# Battery_Charger.net
KiCad netlist of a schematic drawn in Altium Designer
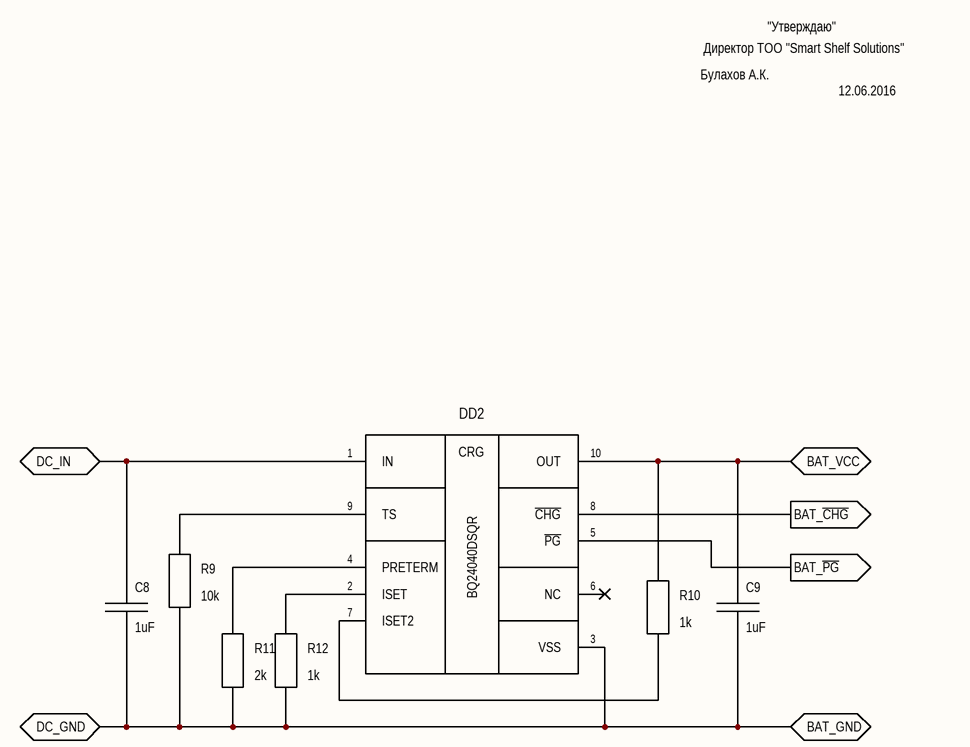
[diagram p0: Battery Charger.SchDoc]

(export (version "E")
  (design (tool "Eeschema 10.0.6"))
  (components
    (comp (ref "C8")
      (value "1uF")
      (footprint "CAPC1608L")
      (description "Capacitor Ceramic 1uF 25V")
      (fields (field (name "TOLERANCE") "±10%") (field (name "MANUFACTURER") "Yageo"))
      (libsource (lib "Capacitors") (part "CC0603KRX5R8BB105"))
    )
    (comp (ref "C9")
      (value "1uF")
      (footprint "CAPC1608L")
      (description "Capacitor Ceramic 1uF 25V")
      (fields (field (name "TOLERANCE") "±10%") (field (name "MANUFACTURER") "Yageo"))
      (libsource (lib "Capacitors") (part "CC0603KRX5R8BB105"))
    )
    (comp (ref "DD2")
      (value "BQ24040DSQR")
      (footprint "WFDFN-10")
      (description "Battery Charger Li-ion/Li Polymer")
      (fields (field (name "MANUFACTURER") "Texas Instruments"))
      (libsource (lib "Power") (part "BQ24040DSQR"))
    )
    (comp (ref "R9")
      (value "10k")
      (footprint "RESC1608L")
      (description "Resistor Ceramic 10k 1608")
      (fields (field (name "MANUFACTURER") "Yageo") (field (name "TOLERANCE") "±5%"))
      (libsource (lib "Resistors") (part "RC0603JR-0710KL"))
    )
    (comp (ref "R10")
      (value "1k")
      (footprint "RESC1608L")
      (description "Resistor Ceramic 1k 1608")
      (fields (field (name "MANUFACTURER") "Yageo") (field (name "TOLERANCE") "±5%"))
      (libsource (lib "Resistors") (part "RC0603JR-071KL"))
    )
    (comp (ref "R11")
      (value "2k")
      (footprint "RESC1608L")
      (description "Resistor Ceramic 2k 1608")
      (fields (field (name "MANUFACTURER") "Yageo") (field (name "TOLERANCE") "±5%"))
      (libsource (lib "Resistors") (part "RC0603JR-072KL"))
    )
    (comp (ref "R12")
      (value "1k")
      (footprint "RESC1608L")
      (description "Resistor Ceramic 1k 1608")
      (fields (field (name "MANUFACTURER") "Yageo") (field (name "TOLERANCE") "±5%"))
      (libsource (lib "Resistors") (part "RC0603JR-071KL"))
    )
  )
  (nets
    (net (code "1") (name "/BAT_GND") (class "Default")
      (node (ref "C8") (pin "2") (pinfunction "2_2") (pintype "passive"))
      (node (ref "C9") (pin "2") (pinfunction "2_2") (pintype "passive"))
      (node (ref "DD2") (pin "3") (pinfunction "VSS_3") (pintype "passive"))
      (node (ref "R11") (pin "2") (pinfunction "2_2") (pintype "passive"))
      (node (ref "R12") (pin "2") (pinfunction "2_2") (pintype "passive"))
      (node (ref "R9") (pin "2") (pinfunction "2_2") (pintype "passive"))
    )
    (net (code "2") (name "/BAT_VCC") (class "Default")
      (node (ref "C9") (pin "1") (pinfunction "1_1") (pintype "passive"))
      (node (ref "DD2") (pin "10") (pinfunction "OUT_10") (pintype "passive"))
      (node (ref "R10") (pin "1") (pinfunction "1_1") (pintype "passive"))
    )
    (net (code "3") (name "/BAT_~{CHG}") (class "Default")
      (node (ref "DD2") (pin "8") (pinfunction "~{CHG}_8") (pintype "passive"))
    )
    (net (code "4") (name "/BAT_~{PG}") (class "Default")
      (node (ref "DD2") (pin "5") (pinfunction "~{PG}_5") (pintype "passive"))
    )
    (net (code "5") (name "/DC_IN") (class "Default")
      (node (ref "C8") (pin "1") (pinfunction "1_1") (pintype "passive"))
      (node (ref "DD2") (pin "1") (pinfunction "IN_1") (pintype "passive"))
    )
    (net (code "6") (name "Net-(DD2-ISET)") (class "Default")
      (node (ref "DD2") (pin "2") (pinfunction "ISET_2") (pintype "passive"))
      (node (ref "R12") (pin "1") (pinfunction "1_1") (pintype "passive"))
    )
    (net (code "7") (name "Net-(DD2-ISET2)") (class "Default")
      (node (ref "DD2") (pin "7") (pinfunction "ISET2_7") (pintype "passive"))
      (node (ref "R10") (pin "2") (pinfunction "2_2") (pintype "passive"))
    )
    (net (code "8") (name "Net-(DD2-PRETERM)") (class "Default")
      (node (ref "DD2") (pin "4") (pinfunction "PRETERM_4") (pintype "passive"))
      (node (ref "R11") (pin "1") (pinfunction "1_1") (pintype "passive"))
    )
    (net (code "9") (name "Net-(DD2-TS)") (class "Default")
      (node (ref "DD2") (pin "9") (pinfunction "TS_9") (pintype "passive"))
      (node (ref "R9") (pin "1") (pinfunction "1_1") (pintype "passive"))
    )
    (net (code "10") (name "unconnected-(DD2-NC-Pad6)") (class "Default")
      (node (ref "DD2") (pin "6") (pinfunction "NC_6") (pintype "passive+no_connect"))
    )
  )
)
